# g_Switched_Cap_BC.net
KiCad netlist of a schematic drawn in EAGLE
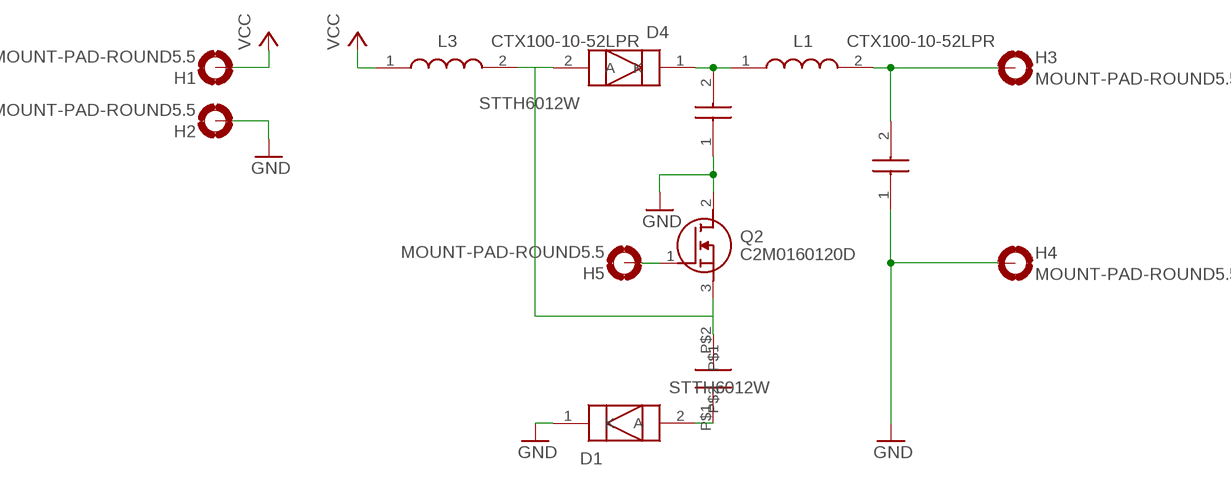
[diagram p0: schematic, sheet 1]

(export (version "E")
  (design (tool "Eeschema 10.0.6"))
  (components
    (comp (ref "C1")
      (value "B32774D4505K000")
      (footprint "eagle-import:B32774D4505K000")
      (fields (field (name "RS_PART_NUMBER") "1726009"))
      (libsource (lib "eagle-import") (part "B32774D4505K000"))
    )
    (comp (ref "C2")
      (value "PH_B32774D4505K000PLACEHOLDER")
      (footprint "eagle-import:TJ4-U1")
      (libsource (lib "eagle-import") (part "PH_B32774D4505K000PLACEHOLDER"))
    )
    (comp (ref "C3")
      (value "B32774D4505K000")
      (footprint "eagle-import:B32774D4505K000")
      (fields (field (name "RS_PART_NUMBER") "1726009"))
      (libsource (lib "eagle-import") (part "B32774D4505K000"))
    )
    (comp (ref "D1")
      (value "STTH6012W")
      (footprint "eagle-import:TO1090P515X1560X2445-2P")
      (fields (field (name "RS_PART_NUMBER") "6870818"))
      (libsource (lib "eagle-import") (part "STTH6012W"))
    )
    (comp (ref "D4")
      (value "STTH6012W")
      (footprint "eagle-import:TO1090P515X1560X2445-2P")
      (fields (field (name "RS_PART_NUMBER") "6870818"))
      (libsource (lib "eagle-import") (part "STTH6012W"))
    )
    (comp (ref "H1")
      (value "MOUNT-PAD-ROUND5.5")
      (footprint "eagle-import:5,5-PAD")
      (libsource (lib "eagle-import") (part "MOUNT-PAD-ROUND5.5"))
    )
    (comp (ref "H2")
      (value "MOUNT-PAD-ROUND5.5")
      (footprint "eagle-import:5,5-PAD")
      (libsource (lib "eagle-import") (part "MOUNT-PAD-ROUND5.5"))
    )
    (comp (ref "H3")
      (value "MOUNT-PAD-ROUND5.5")
      (footprint "eagle-import:5,5-PAD")
      (libsource (lib "eagle-import") (part "MOUNT-PAD-ROUND5.5"))
    )
    (comp (ref "H4")
      (value "MOUNT-PAD-ROUND5.5")
      (footprint "eagle-import:5,5-PAD")
      (libsource (lib "eagle-import") (part "MOUNT-PAD-ROUND5.5"))
    )
    (comp (ref "H5")
      (value "MOUNT-PAD-ROUND5.5")
      (footprint "eagle-import:5,5-PAD")
      (libsource (lib "eagle-import") (part "MOUNT-PAD-ROUND5.5"))
    )
    (comp (ref "L1")
      (value "CTX100-10-52LPR")
      (footprint "eagle-import:CTX1001052LPR")
      (libsource (lib "eagle-import") (part "CTX100-10-52LPR"))
    )
    (comp (ref "L3")
      (value "CTX100-10-52LPR")
      (footprint "eagle-import:CTX1001052LPR")
      (libsource (lib "eagle-import") (part "CTX100-10-52LPR"))
    )
    (comp (ref "Q2")
      (value "C2M0160120D")
      (footprint "eagle-import:TO544P521X1594X2550-3P")
      (fields (field (name "RS_PART_NUMBER") "1629709"))
      (libsource (lib "eagle-import") (part "C2M0160120D"))
    )
  )
  (nets
    (net (code "1") (name "GND") (class "Default")
      (node (ref "C1") (pin "1") (pinfunction "1_1") (pintype "bidirectional"))
      (node (ref "C3") (pin "1") (pinfunction "1_1") (pintype "bidirectional"))
      (node (ref "D1") (pin "1") (pinfunction "K_1") (pintype "bidirectional"))
      (node (ref "H2") (pin "B5,5") (pinfunction "MOUNT_B5,5") (pintype "passive"))
      (node (ref "H4") (pin "B5,5") (pinfunction "MOUNT_B5,5") (pintype "passive"))
      (node (ref "Q2") (pin "2") (pinfunction "D_2") (pintype "bidirectional"))
    )
    (net (code "2") (name "Net-(D1-A)") (class "Default")
      (node (ref "C2") (pin "P$1") (pinfunction "P$1_P$1") (pintype "bidirectional"))
      (node (ref "D1") (pin "2") (pinfunction "A_2") (pintype "bidirectional"))
    )
    (net (code "3") (name "Net-(D4-A)") (class "Default")
      (node (ref "C2") (pin "P$2") (pinfunction "P$2_P$2") (pintype "bidirectional"))
      (node (ref "D4") (pin "2") (pinfunction "A_2") (pintype "bidirectional"))
      (node (ref "L3") (pin "2") (pinfunction "2_2") (pintype "bidirectional"))
      (node (ref "Q2") (pin "3") (pinfunction "S_3") (pintype "bidirectional"))
    )
    (net (code "4") (name "Net-(D4-K)") (class "Default")
      (node (ref "C1") (pin "2") (pinfunction "2_2") (pintype "bidirectional"))
      (node (ref "D4") (pin "1") (pinfunction "K_1") (pintype "bidirectional"))
      (node (ref "L1") (pin "1") (pinfunction "1_1") (pintype "bidirectional"))
    )
    (net (code "5") (name "Net-(H3-MOUNT)") (class "Default")
      (node (ref "C3") (pin "2") (pinfunction "2_2") (pintype "bidirectional"))
      (node (ref "H3") (pin "B5,5") (pinfunction "MOUNT_B5,5") (pintype "passive"))
      (node (ref "L1") (pin "2") (pinfunction "2_2") (pintype "bidirectional"))
    )
    (net (code "6") (name "Net-(H5-MOUNT)") (class "Default")
      (node (ref "H5") (pin "B5,5") (pinfunction "MOUNT_B5,5") (pintype "passive"))
      (node (ref "Q2") (pin "1") (pinfunction "G_1") (pintype "bidirectional"))
    )
    (net (code "7") (name "VCC") (class "Default")
      (node (ref "H1") (pin "B5,5") (pinfunction "MOUNT_B5,5") (pintype "passive"))
      (node (ref "L3") (pin "1") (pinfunction "1_1") (pintype "bidirectional"))
    )
  )
)
